# Ethernet.net
KiCad netlist of a schematic drawn in Altium Designer
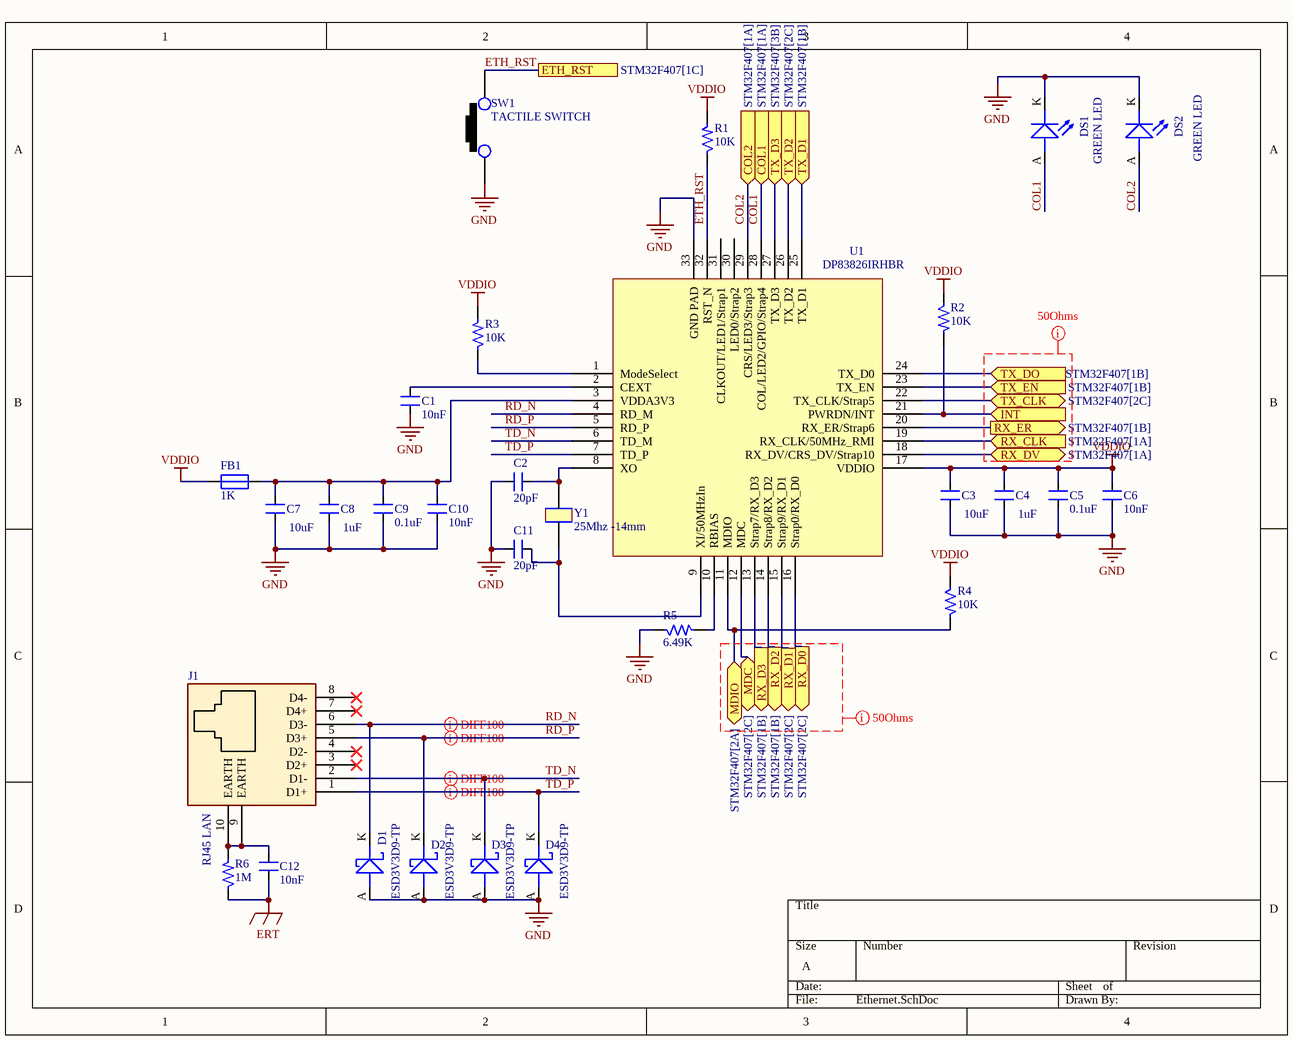
[diagram p0: Ethernet.SchDoc]

(export (version "E")
  (design (tool "Eeschema 10.0.6"))
  (components
    (comp (ref "C1")
      (value "10nF")
      (footprint "CAP_0805")
      (description "10000pF ±10% 50V Ceramic Capacitor X7R 0805 (2012 Metric)")
      (fields
        (field (name "MANUFACTURER") "Samsung")
        (field (name "MANUFACTURER PART NUMBER") "C0805C103K5RECAUTO")
      )
      (libsource (lib "ESTEEMPCBLIB") (part "CAP_10nF-50V-10%-0805"))
    )
    (comp (ref "C2")
      (value "20pF")
      (footprint "CAP_0805")
      (description "±10% 50V Ceramic Capacitor C0G, NP0 0805 (2012 Metric)")
      (fields
        (field (name "MANUFACTURER") "AVX Corporation")
        (field (name "MANUFACTURER PART NUMBER") "08055A200KAT2A")
      )
      (libsource (lib "ESTEEMPCBLIB") (part "CAP_20pF-50V-10%-0805"))
    )
    (comp (ref "C3")
      (value "10uF")
      (footprint "CAP_1206")
      (description "10µF ±10% 50V Ceramic Capacitor X7R 1206 (3216 Metric)")
      (fields
        (field (name "MANUFACTURER") "KEMET")
        (field (name "MANUFACTURER PART NUMBER") "CL31B106KBHNNNE")
      )
      (libsource (lib "ESTEEMPCBLIB") (part "CAP_10uF-50V-10%-1206"))
    )
    (comp (ref "C4")
      (value "1uF")
      (footprint "CAP_0805")
      (description "1µF ±5% 50V Ceramic Capacitor X7R 0805 (2012 Metric)")
      (fields
        (field (name "MANUFACTURER") "Samsung")
        (field (name "MANUFACTURER PART NUMBER") "CC0805JKX7R9BB105")
      )
      (libsource (lib "ESTEEMPCBLIB") (part "CAP_1uF-50V-5%-0805"))
    )
    (comp (ref "C5")
      (value "0.1uF")
      (footprint "CAP_0805")
      (description "0.1µF ±5% 50V Ceramic Capacitor X7R 0805 (2012 Metric)")
      (fields
        (field (name "MANUFACTURER") "AVX Corporation")
        (field (name "MANUFACTURER PART NUMBER") "08055C104JAT4A")
      )
      (libsource (lib "ESTEEMPCBLIB") (part "CAP_0.1uF-50V-5%-0805"))
    )
    (comp (ref "C6")
      (value "10nF")
      (footprint "CAP_0805")
      (description "10000pF ±10% 50V Ceramic Capacitor X7R 0805 (2012 Metric)")
      (fields
        (field (name "MANUFACTURER") "Samsung")
        (field (name "MANUFACTURER PART NUMBER") "C0805C103K5RECAUTO")
      )
      (libsource (lib "ESTEEMPCBLIB") (part "CAP_10nF-50V-10%-0805"))
    )
    (comp (ref "C7")
      (value "10uF")
      (footprint "CAP_1206")
      (description "10µF ±10% 50V Ceramic Capacitor X7R 1206 (3216 Metric)")
      (fields
        (field (name "MANUFACTURER") "KEMET")
        (field (name "MANUFACTURER PART NUMBER") "CL31B106KBHNNNE")
      )
      (libsource (lib "ESTEEMPCBLIB") (part "CAP_10uF-50V-10%-1206"))
    )
    (comp (ref "C8")
      (value "1uF")
      (footprint "CAP_0805")
      (description "1µF ±5% 50V Ceramic Capacitor X7R 0805 (2012 Metric)")
      (fields
        (field (name "MANUFACTURER") "Samsung")
        (field (name "MANUFACTURER PART NUMBER") "CC0805JKX7R9BB105")
      )
      (libsource (lib "ESTEEMPCBLIB") (part "CAP_1uF-50V-5%-0805"))
    )
    (comp (ref "C9")
      (value "0.1uF")
      (footprint "CAP_0805")
      (description "0.1µF ±5% 50V Ceramic Capacitor X7R 0805 (2012 Metric)")
      (fields
        (field (name "MANUFACTURER") "AVX Corporation")
        (field (name "MANUFACTURER PART NUMBER") "08055C104JAT4A")
      )
      (libsource (lib "ESTEEMPCBLIB") (part "CAP_0.1uF-50V-5%-0805"))
    )
    (comp (ref "C10")
      (value "10nF")
      (footprint "CAP_0805")
      (description "10000pF ±10% 50V Ceramic Capacitor X7R 0805 (2012 Metric)")
      (fields
        (field (name "MANUFACTURER") "Samsung")
        (field (name "MANUFACTURER PART NUMBER") "C0805C103K5RECAUTO")
      )
      (libsource (lib "ESTEEMPCBLIB") (part "CAP_10nF-50V-10%-0805"))
    )
    (comp (ref "C11")
      (value "20pF")
      (footprint "CAP_0805")
      (description "±10% 50V Ceramic Capacitor C0G, NP0 0805 (2012 Metric)")
      (fields
        (field (name "MANUFACTURER") "AVX Corporation")
        (field (name "MANUFACTURER PART NUMBER") "08055A200KAT2A")
      )
      (libsource (lib "ESTEEMPCBLIB") (part "CAP_20pF-50V-10%-0805"))
    )
    (comp (ref "C12")
      (value "10nF")
      (footprint "CAP_P196_102X287_H332_RAD_TH")
      (description "10000pF ±10% 1000V (1kV) Ceramic Capacitor X7R Radial")
      (fields
        (field (name "MANUFACTURER") "Yageo")
        (field (name "MANUFACTURER PART NUMBER") "RDER73A103K2K1H03B")
      )
      (libsource (lib "ESTEEMPCBLIB") (part "CAP_10nF-1KV-10%-RAD-TH"))
    )
    (comp (ref "D1")
      (value "ESD3V3D9-TP")
      (footprint "DIO_SOD-923")
      (description "TVS DIODE 3.3V 8.8V SOD923")
      (fields (field (name "MANUFACTURER") "Micro Commercial Co"))
      (libsource (lib "ESTEEMPCBLIB") (part "DIO-T_3.3V-8.8V-10A-SOD923"))
    )
    (comp (ref "D2")
      (value "ESD3V3D9-TP")
      (footprint "DIO_SOD-923")
      (description "TVS DIODE 3.3V 8.8V SOD923")
      (fields (field (name "MANUFACTURER") "Micro Commercial Co"))
      (libsource (lib "ESTEEMPCBLIB") (part "DIO-T_3.3V-8.8V-10A-SOD923"))
    )
    (comp (ref "D3")
      (value "ESD3V3D9-TP")
      (footprint "DIO_SOD-923")
      (description "TVS DIODE 3.3V 8.8V SOD923")
      (fields (field (name "MANUFACTURER") "Micro Commercial Co"))
      (libsource (lib "ESTEEMPCBLIB") (part "DIO-T_3.3V-8.8V-10A-SOD923"))
    )
    (comp (ref "D4")
      (value "ESD3V3D9-TP")
      (footprint "DIO_SOD-923")
      (description "TVS DIODE 3.3V 8.8V SOD923")
      (fields (field (name "MANUFACTURER") "Micro Commercial Co"))
      (libsource (lib "ESTEEMPCBLIB") (part "DIO-T_3.3V-8.8V-10A-SOD923"))
    )
    (comp (ref "DS1")
      (value "GREEN LED")
      (footprint "LED_0805")
      (description "Green 569nm LED Indication - Discrete 2.1V 0805 (2012 Metric)")
      (fields
        (field (name "MANUFACTURER") "Vishay Lite-On")
        (field (name "MANUFACTURER PART NUMBER") "LTST-C171GKT")
      )
      (libsource (lib "ESTEEMPCBLIB") (part "LED_GREEN-2.2-20mA-0805"))
    )
    (comp (ref "DS2")
      (value "GREEN LED")
      (footprint "LED_0805")
      (description "Green 569nm LED Indication - Discrete 2.1V 0805 (2012 Metric)")
      (fields
        (field (name "MANUFACTURER") "Vishay Lite-On")
        (field (name "MANUFACTURER PART NUMBER") "LTST-C171GKT")
      )
      (libsource (lib "ESTEEMPCBLIB") (part "LED_GREEN-2.2-20mA-0805"))
    )
    (comp (ref "FB1")
      (value "1K")
      (footprint "IND_0805")
      (description "1 kOhms @ 100MHz 1 Power Line Ferrite Bead 0805 (2012 Metric) 1.6A")
      (fields
        (field (name "MANUFACTURER") "Laird")
        (field (name "MANUFACTURER PART NUMBER") "BLM21SP102SH1D")
      )
      (libsource (lib "ESTEEMPCBLIB") (part "FB_1K-100MHZ-1.6A-0805"))
    )
    (comp (ref "J1")
      (value "RJ45 LAN")
      (footprint "CON10_P106_RJ45_TH_ST")
      (description "8 Pins, 2 Row 2.54mm Pitch, right angle Connector, male")
      (fields
        (field (name "MANUFACTURER") "Assmann")
        (field (name "MANUFACTURER PART NUMBER") "A-2004-2-4-LPS-N-R")
      )
      (libsource (lib "ESTEEMPCBLIB") (part "CON-SKT-RJ_8C8P-RA-TH"))
    )
    (comp (ref "R1")
      (value "10K")
      (footprint "RES_0805")
      (description "10 kOhms ±1% 0.125W, 1/8W Chip Resistor 0805 (2012 Metric) Automotive AEC-Q200 Thick Film")
      (fields (field (name "MANUFACTURER") "CTS") (field (name "MANUFACTURER PART NUMBER") "WR08X1002FTL"))
      (libsource (lib "ESTEEMPCBLIB") (part "RES_10K-0.125W-1%-0805"))
    )
    (comp (ref "R2")
      (value "10K")
      (footprint "RES_0603")
      (description "10 kOhms ±1% 0.1W, 1/10W Chip Resistor 0603 (1608 Metric) Automotive AEC-Q200 Thick Film")
      (fields (field (name "MANUFACTURER") "Walsin") (field (name "MANUFACTURER PART NUMBER") "WR06X1002FTL"))
      (libsource (lib "ESTEEMPCBLIB") (part "RES_10K-0.1W-1%-0603"))
    )
    (comp (ref "R3")
      (value "10K")
      (footprint "RES_0805")
      (description "10 kOhms ±1% 0.125W, 1/8W Chip Resistor 0805 (2012 Metric) Automotive AEC-Q200 Thick Film")
      (fields (field (name "MANUFACTURER") "CTS") (field (name "MANUFACTURER PART NUMBER") "WR08X1002FTL"))
      (libsource (lib "ESTEEMPCBLIB") (part "RES_10K-0.125W-1%-0805"))
    )
    (comp (ref "R4")
      (value "10K")
      (footprint "RES_0603")
      (description "10 kOhms ±1% 0.1W, 1/10W Chip Resistor 0603 (1608 Metric) Automotive AEC-Q200 Thick Film")
      (fields (field (name "MANUFACTURER") "Walsin") (field (name "MANUFACTURER PART NUMBER") "WR06X1002FTL"))
      (libsource (lib "ESTEEMPCBLIB") (part "RES_10K-0.1W-1%-0603"))
    )
    (comp (ref "R5")
      (value "6.49K")
      (footprint "RES_0805")
      (description "6.49 kOhms ±1% 0.125W, 1/8W Chip Resistor 0805 (2012 Metric) Moisture Resistant Thick Film")
      (fields
        (field (name "MANUFACTURER") "Stackpole Electronics")
        (field (name "MANUFACTURER PART NUMBER") "RC0805FR-076K49L")
      )
      (libsource (lib "ESTEEMPCBLIB") (part "RES_6.49K-0.125W-1%-0805"))
    )
    (comp (ref "R6")
      (value "1M")
      (footprint "RES_1206")
      (fields (field (name "MANUFACTURER") "Walsin") (field (name "MANUFACTURER PART NUMBER") "WR12X1004FTL"))
      (libsource (lib "ESTEEMPCBLIB") (part "RES_1M-0.25W-1%-1206"))
    )
    (comp (ref "SW1")
      (value "TACTILE SWITCH")
      (footprint "SW_342_SMD")
      (description "Tactile Switch SPST-NO Top Actuated Surface Mount")
      (fields
        (field (name "MANUFACTURER") "ITT C&K")
        (field (name "MANUFACTURER PART NUMBER") "RS-282G05A3-SMRT")
      )
      (libsource (lib "ESTEEMPCBLIB") (part "SW1_RS-282G05A3-SMRT-SMD"))
    )
    (comp (ref "U1")
      (value "DP83826IRHBR")
      (footprint "VQFN32_19_218_23X9_SMD")
      (fields (field (name "MANUFACTURER") "Texas Instruments"))
      (libsource (lib "ESTEEMPCBLIB") (part "IC_DP83826IRHBR"))
    )
    (comp (ref "Y1")
      (value "25Mhz -14mm")
      (footprint "XTAL_314_240X47_SMD")
      (description "25MHz ±30ppm Crystal 20pF 30 Ohms HC-49/US")
      (fields
        (field (name "MANUFACTURER") "Abracon")
        (field (name "MANUFACTURER PART NUMBER") "FOXSDLF/250F-20")
      )
      (libsource (lib "ESTEEMPCBLIB") (part "XTAL_25Mhz-FOXSDLF/250F-20"))
    )
  )
  (nets
    (net (code "1") (name "/COL1") (class "Default")
      (node (ref "DS1") (pin "A") (pinfunction "ANODE_A") (pintype "passive"))
      (node (ref "U1") (pin "28") (pinfunction "COL/LED2/GPIO/Strap4_28") (pintype "passive"))
    )
    (net (code "2") (name "/COL2") (class "Default")
      (node (ref "DS2") (pin "A") (pinfunction "ANODE_A") (pintype "passive"))
      (node (ref "U1") (pin "29") (pinfunction "CRS/LED3/Strap3_29") (pintype "passive"))
    )
    (net (code "3") (name "/ETH_RST") (class "Default")
      (node (ref "R1") (pin "1") (pinfunction "1_1") (pintype "passive"))
      (node (ref "SW1") (pin "2") (pinfunction "2_2") (pintype "passive"))
      (node (ref "U1") (pin "32") (pinfunction "RST_N_32") (pintype "passive"))
    )
    (net (code "4") (name "/INT") (class "Default")
      (node (ref "R2") (pin "2") (pinfunction "2_2") (pintype "passive"))
      (node (ref "U1") (pin "21") (pinfunction "PWRDN/INT_21") (pintype "passive"))
    )
    (net (code "5") (name "/MDC") (class "Default")
      (node (ref "U1") (pin "12") (pinfunction "MDC_12") (pintype "passive"))
    )
    (net (code "6") (name "/MDIO") (class "Default")
      (node (ref "R4") (pin "2") (pinfunction "2_2") (pintype "passive"))
      (node (ref "U1") (pin "11") (pinfunction "MDIO_11") (pintype "passive"))
    )
    (net (code "7") (name "/RD_N") (class "Default")
      (node (ref "D1") (pin "K") (pinfunction "K_K") (pintype "passive"))
      (node (ref "J1") (pin "6") (pinfunction "D3-_6") (pintype "passive"))
      (node (ref "U1") (pin "4") (pinfunction "RD_M_4") (pintype "passive"))
    )
    (net (code "8") (name "/RD_P") (class "Default")
      (node (ref "D2") (pin "K") (pinfunction "K_K") (pintype "passive"))
      (node (ref "J1") (pin "5") (pinfunction "D3+_5") (pintype "passive"))
      (node (ref "U1") (pin "5") (pinfunction "RD_P_5") (pintype "passive"))
    )
    (net (code "9") (name "/RX_CLK") (class "Default")
      (node (ref "U1") (pin "19") (pinfunction "RX_CLK/50MHz_RMI_19") (pintype "passive"))
    )
    (net (code "10") (name "/RX_D0") (class "Default")
      (node (ref "U1") (pin "16") (pinfunction "Strap0/RX_D0_16") (pintype "passive"))
    )
    (net (code "11") (name "/RX_D1") (class "Default")
      (node (ref "U1") (pin "15") (pinfunction "Strap9/RX_D1_15") (pintype "passive"))
    )
    (net (code "12") (name "/RX_D2") (class "Default")
      (node (ref "U1") (pin "14") (pinfunction "Strap8/RX_D2_14") (pintype "passive"))
    )
    (net (code "13") (name "/RX_D3") (class "Default")
      (node (ref "U1") (pin "13") (pinfunction "Strap7/RX_D3_13") (pintype "passive"))
    )
    (net (code "14") (name "/RX_DV") (class "Default")
      (node (ref "U1") (pin "18") (pinfunction "RX_DV/CRS_DV/Strap10_18") (pintype "passive"))
    )
    (net (code "15") (name "/RX_ER") (class "Default")
      (node (ref "U1") (pin "20") (pinfunction "RX_ER/Strap6_20") (pintype "passive"))
    )
    (net (code "16") (name "/TD_N") (class "Default")
      (node (ref "D3") (pin "K") (pinfunction "K_K") (pintype "passive"))
      (node (ref "J1") (pin "2") (pinfunction "D1-_2") (pintype "passive"))
      (node (ref "U1") (pin "6") (pinfunction "TD_M_6") (pintype "passive"))
    )
    (net (code "17") (name "/TD_P") (class "Default")
      (node (ref "D4") (pin "K") (pinfunction "K_K") (pintype "passive"))
      (node (ref "J1") (pin "1") (pinfunction "D1+_1") (pintype "passive"))
      (node (ref "U1") (pin "7") (pinfunction "TD_P_7") (pintype "passive"))
    )
    (net (code "18") (name "/TX_CLK") (class "Default")
      (node (ref "U1") (pin "22") (pinfunction "TX_CLK/Strap5_22") (pintype "passive"))
    )
    (net (code "19") (name "/TX_D1") (class "Default")
      (node (ref "U1") (pin "25") (pinfunction "TX_D1_25") (pintype "passive"))
    )
    (net (code "20") (name "/TX_D2") (class "Default")
      (node (ref "U1") (pin "26") (pinfunction "TX_D2_26") (pintype "passive"))
    )
    (net (code "21") (name "/TX_D3") (class "Default")
      (node (ref "U1") (pin "27") (pinfunction "TX_D3_27") (pintype "passive"))
    )
    (net (code "22") (name "/TX_DO") (class "Default")
      (node (ref "U1") (pin "24") (pinfunction "TX_D0_24") (pintype "passive"))
    )
    (net (code "23") (name "/TX_EN") (class "Default")
      (node (ref "U1") (pin "23") (pinfunction "TX_EN_23") (pintype "passive"))
    )
    (net (code "24") (name "ERT") (class "Default")
      (node (ref "C12") (pin "1") (pinfunction "1_1") (pintype "passive"))
      (node (ref "R6") (pin "1") (pinfunction "1_1") (pintype "passive"))
    )
    (net (code "25") (name "GND") (class "Default")
      (node (ref "C1") (pin "1") (pinfunction "1_1") (pintype "passive"))
      (node (ref "C10") (pin "1") (pinfunction "1_1") (pintype "passive"))
      (node (ref "C11") (pin "1") (pinfunction "1_1") (pintype "passive"))
      (node (ref "C2") (pin "1") (pinfunction "1_1") (pintype "passive"))
      (node (ref "C3") (pin "1") (pinfunction "1_1") (pintype "passive"))
      (node (ref "C4") (pin "1") (pinfunction "1_1") (pintype "passive"))
      (node (ref "C5") (pin "1") (pinfunction "1_1") (pintype "passive"))
      (node (ref "C6") (pin "1") (pinfunction "1_1") (pintype "passive"))
      (node (ref "C7") (pin "1") (pinfunction "1_1") (pintype "passive"))
      (node (ref "C8") (pin "1") (pinfunction "1_1") (pintype "passive"))
      (node (ref "C9") (pin "1") (pinfunction "1_1") (pintype "passive"))
      (node (ref "D1") (pin "A") (pinfunction "A_A") (pintype "passive"))
      (node (ref "D2") (pin "A") (pinfunction "A_A") (pintype "passive"))
      (node (ref "D3") (pin "A") (pinfunction "A_A") (pintype "passive"))
      (node (ref "D4") (pin "A") (pinfunction "A_A") (pintype "passive"))
      (node (ref "DS1") (pin "K") (pinfunction "CATHODE_K") (pintype "passive"))
      (node (ref "DS2") (pin "K") (pinfunction "CATHODE_K") (pintype "passive"))
      (node (ref "R5") (pin "1") (pinfunction "1_1") (pintype "passive"))
      (node (ref "SW1") (pin "1") (pinfunction "1_1") (pintype "passive"))
      (node (ref "U1") (pin "33") (pinfunction "GND_PAD_33") (pintype "passive"))
    )
    (net (code "26") (name "Net-(C12-Pad2)") (class "Default")
      (node (ref "C12") (pin "2") (pinfunction "2_2") (pintype "passive"))
      (node (ref "J1") (pin "10") (pinfunction "EARTH_10") (pintype "passive"))
      (node (ref "J1") (pin "9") (pinfunction "EARTH_9") (pintype "passive"))
      (node (ref "R6") (pin "2") (pinfunction "2_2") (pintype "passive"))
    )
    (net (code "27") (name "Net-(U1-CEXT)") (class "Default")
      (node (ref "C1") (pin "2") (pinfunction "2_2") (pintype "passive"))
      (node (ref "U1") (pin "2") (pinfunction "CEXT_2") (pintype "passive"))
    )
    (net (code "28") (name "Net-(U1-ModeSelect)") (class "Default")
      (node (ref "R3") (pin "1") (pinfunction "1_1") (pintype "passive"))
      (node (ref "U1") (pin "1") (pinfunction "ModeSelect_1") (pintype "passive"))
    )
    (net (code "29") (name "Net-(U1-RBIAS)") (class "Default")
      (node (ref "R5") (pin "2") (pinfunction "2_2") (pintype "passive"))
      (node (ref "U1") (pin "10") (pinfunction "RBIAS_10") (pintype "passive"))
    )
    (net (code "30") (name "Net-(U1-VDDA3V3)") (class "Default")
      (node (ref "C10") (pin "2") (pinfunction "2_2") (pintype "passive"))
      (node (ref "C7") (pin "2") (pinfunction "2_2") (pintype "passive"))
      (node (ref "C8") (pin "2") (pinfunction "2_2") (pintype "passive"))
      (node (ref "C9") (pin "2") (pinfunction "2_2") (pintype "passive"))
      (node (ref "FB1") (pin "2") (pinfunction "2_2") (pintype "passive"))
      (node (ref "U1") (pin "3") (pinfunction "VDDA3V3_3") (pintype "passive"))
    )
    (net (code "31") (name "Net-(U1-XI{slash}50MHzIn)") (class "Default")
      (node (ref "C11") (pin "2") (pinfunction "2_2") (pintype "passive"))
      (node (ref "U1") (pin "9") (pinfunction "XI/50MHzIn_9") (pintype "passive"))
      (node (ref "Y1") (pin "2") (pinfunction "2_2") (pintype "passive"))
    )
    (net (code "32") (name "Net-(U1-XO)") (class "Default")
      (node (ref "C2") (pin "2") (pinfunction "2_2") (pintype "passive"))
      (node (ref "U1") (pin "8") (pinfunction "XO_8") (pintype "passive"))
      (node (ref "Y1") (pin "1") (pinfunction "1_1") (pintype "passive"))
    )
    (net (code "33") (name "VDDIO") (class "Default")
      (node (ref "C3") (pin "2") (pinfunction "2_2") (pintype "passive"))
      (node (ref "C4") (pin "2") (pinfunction "2_2") (pintype "passive"))
      (node (ref "C5") (pin "2") (pinfunction "2_2") (pintype "passive"))
      (node (ref "C6") (pin "2") (pinfunction "2_2") (pintype "passive"))
      (node (ref "FB1") (pin "1") (pinfunction "1_1") (pintype "passive"))
      (node (ref "R1") (pin "2") (pinfunction "2_2") (pintype "passive"))
      (node (ref "R2") (pin "1") (pinfunction "1_1") (pintype "passive"))
      (node (ref "R3") (pin "2") (pinfunction "2_2") (pintype "passive"))
      (node (ref "R4") (pin "1") (pinfunction "1_1") (pintype "passive"))
      (node (ref "U1") (pin "17") (pinfunction "VDDIO_17") (pintype "passive"))
    )
    (net (code "34") (name "unconnected-(J1-D2+-Pad3)") (class "Default")
      (node (ref "J1") (pin "3") (pinfunction "D2+_3") (pintype "passive+no_connect"))
    )
    (net (code "35") (name "unconnected-(J1-D2--Pad4)") (class "Default")
      (node (ref "J1") (pin "4") (pinfunction "D2-_4") (pintype "passive+no_connect"))
    )
    (net (code "36") (name "unconnected-(J1-D4+-Pad7)") (class "Default")
      (node (ref "J1") (pin "7") (pinfunction "D4+_7") (pintype "passive+no_connect"))
    )
    (net (code "37") (name "unconnected-(J1-D4--Pad8)") (class "Default")
      (node (ref "J1") (pin "8") (pinfunction "D4-_8") (pintype "passive+no_connect"))
    )
    (net (code "38") (name "unconnected-(U1-CLKOUT{slash}LED1{slash}Strap1-Pad31)") (class "Default")
      (node (ref "U1") (pin "31") (pinfunction "CLKOUT/LED1/Strap1_31") (pintype "passive"))
    )
    (net (code "39") (name "unconnected-(U1-LED0{slash}Strap2-Pad30)") (class "Default")
      (node (ref "U1") (pin "30") (pinfunction "LED0/Strap2_30") (pintype "passive"))
    )
  )
)
